# Symmetric_PS.net
KiCad netlist of a schematic drawn in Altium Designer
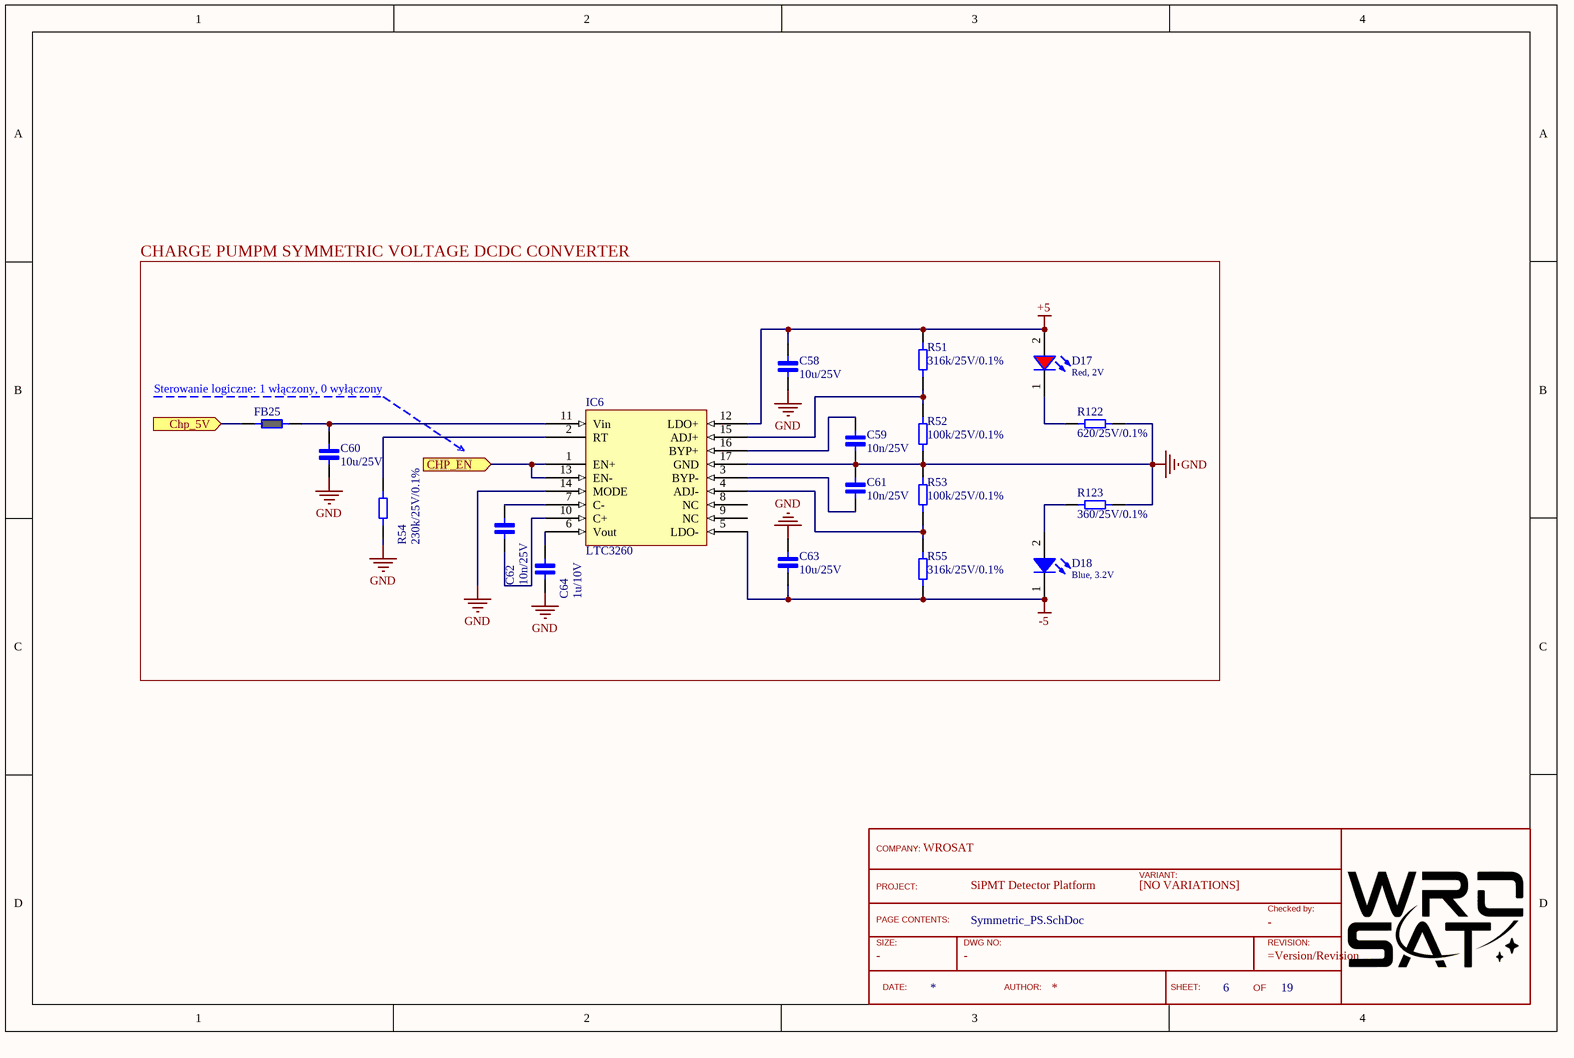
[diagram p0: Symmetric_PS.SchDoc]

(export (version "E")
  (design (tool "Eeschema 10.0.6"))
  (components
    (comp (ref "C58")
      (value "10u/25V")
      (footprint "CAP_0805")
      (description "Ceramic Capacitor 10uF / 0805 / 25V / ±5%, Wurth Elektronik MLCC")
      (libsource (lib "Cubesat_lib") (part "Cap_0805_10u_25v"))
    )
    (comp (ref "C59")
      (value "10n/25V")
      (footprint "Cap_0402")
      (description "Ceramic Capacitor 10n / 0402 / 25V / ±5%, Wurth Elektronik MLCC")
      (libsource (lib "Cubesat_lib") (part "Cap_0402_10n"))
    )
    (comp (ref "C60")
      (value "10u/25V")
      (footprint "CAP_0805")
      (description "Ceramic Capacitor 10uF / 0805 / 25V / ±5%, Wurth Elektronik MLCC")
      (libsource (lib "Cubesat_lib") (part "Cap_0805_10u_25v"))
    )
    (comp (ref "C61")
      (value "10n/25V")
      (footprint "Cap_0402")
      (description "Ceramic Capacitor 10n / 0402 / 25V / ±5%, Wurth Elektronik MLCC")
      (libsource (lib "Cubesat_lib") (part "Cap_0402_10n"))
    )
    (comp (ref "C62")
      (value "10n/25V")
      (footprint "Cap_0402")
      (description "Ceramic Capacitor 10n / 0402 / 25V / ±5%, Wurth Elektronik MLCC")
      (libsource (lib "Cubesat_lib") (part "Cap_0402_10n"))
    )
    (comp (ref "C63")
      (value "10u/25V")
      (footprint "CAP_0805")
      (description "Ceramic Capacitor 10uF / 0805 / 25V / ±5%, Wurth Elektronik MLCC")
      (libsource (lib "Cubesat_lib") (part "Cap_0805_10u_25v"))
    )
    (comp (ref "C64")
      (value "1u/10V")
      (footprint "Cap_0402")
      (description "Ceramic Capacitor 1uF / 0402 / 10V / ±5%, Wurth Elektronik MLCC")
      (libsource (lib "Cubesat_lib") (part "Cap_0402_1u"))
    )
    (comp (ref "D17")
      (value "Red, 2V")
      (footprint "WL-SMCW_0603_H=0.7mm")
      (description "WL-SMCW SMT Mono-color Chip LED Waterclear, size 0603, Red, 2V, 140deg")
      (fields (field (name "PART NUMBER") "150060RS75000") (field (name "PUBLISHER") "Wurth Elektronik"))
      (libsource (lib "LEDS") (part "150060RS75000"))
    )
    (comp (ref "D18")
      (value "Blue, 3.2V")
      (footprint "WL-SMCW_0603_H=0.7mm")
      (description "WL-SMCW SMT Mono-color Chip LED Waterclear, size 0603, Blue, 3.2V, 140deg")
      (fields (field (name "PART NUMBER") "150060BS75000") (field (name "PUBLISHER") "Wurth Elektronik"))
      (libsource (lib "LEDS") (part "150060BS75000"))
    )
    (comp (ref "FB25")
      (value "Ferrite_bead_0402")
      (footprint "FERRITE_0402")
      (description "Ferrite bead, wurth 74269241102")
      (libsource (lib "Cubesat_lib") (part "Ferrite_bead_0402"))
    )
    (comp (ref "IC6")
      (value "LTC3260")
      (footprint "MSOP-16")
      (description "Charge pump, low noise")
      (libsource (lib "Cubesat_lib") (part "LTC3260"))
    )
    (comp (ref "R51")
      (value "316k/25V/0.1%")
      (footprint "RES_0402")
      (description "Vishay, thin film resistor 316k/25V/0.1%")
      (libsource (lib "Cubesat_lib") (part "Res_0402_316k"))
    )
    (comp (ref "R52")
      (value "100k/25V/0.1%")
      (footprint "RES_0402")
      (description "Vishay, thin film resistor 100k/25V/0.1%")
      (libsource (lib "Cubesat_lib") (part "Res_0402_100k"))
    )
    (comp (ref "R53")
      (value "100k/25V/0.1%")
      (footprint "RES_0402")
      (description "Vishay, thin film resistor 100k/25V/0.1%")
      (libsource (lib "Cubesat_lib") (part "Res_0402_100k"))
    )
    (comp (ref "R54")
      (value "230k/25V/0.1%")
      (footprint "RES_0402")
      (description "Vishay, thin film resistor 230k/25V/0.1%")
      (libsource (lib "Cubesat_lib") (part "Res_0402_230k"))
    )
    (comp (ref "R55")
      (value "316k/25V/0.1%")
      (footprint "RES_0402")
      (description "Vishay, thin film resistor 316k/25V/0.1%")
      (libsource (lib "Cubesat_lib") (part "Res_0402_316k"))
    )
    (comp (ref "R122")
      (value "620/25V/0.1%")
      (footprint "RES_0402")
      (description "Vishay, thin film resistor 1/25V/0.1%")
      (libsource (lib "") (part "Res_0402_1_1"))
    )
    (comp (ref "R123")
      (value "360/25V/0.1%")
      (footprint "RES_0402")
      (description "Vishay, thin film resistor 1/25V/0.1%")
      (libsource (lib "Cubesat_lib") (part "Res_0402_1"))
    )
  )
  (nets
    (net (code "1") (name "+5") (class "Default")
      (node (ref "C58") (pin "2") (pinfunction "2_2") (pintype "passive"))
      (node (ref "D17") (pin "2") (pinfunction "A_2") (pintype "passive"))
      (node (ref "IC6") (pin "12") (pinfunction "LDO+_12") (pintype "input"))
      (node (ref "R51") (pin "2") (pinfunction "2_2") (pintype "passive"))
    )
    (net (code "2") (name "-5") (class "Default")
      (node (ref "C63") (pin "1") (pinfunction "1_1") (pintype "passive"))
      (node (ref "D18") (pin "1") (pinfunction "K_1") (pintype "passive"))
      (node (ref "IC6") (pin "5") (pinfunction "LDO-_5") (pintype "input"))
      (node (ref "R55") (pin "1") (pinfunction "1_1") (pintype "passive"))
    )
    (net (code "3") (name "/CHP_EN") (class "Default")
      (node (ref "IC6") (pin "1") (pinfunction "EN+_1") (pintype "passive"))
      (node (ref "IC6") (pin "13") (pinfunction "EN-_13") (pintype "input"))
    )
    (net (code "4") (name "/Chp_5V") (class "Default")
      (node (ref "FB25") (pin "1") (pinfunction "1_1") (pintype "passive"))
    )
    (net (code "5") (name "GND") (class "Default")
      (node (ref "C58") (pin "1") (pinfunction "1_1") (pintype "passive"))
      (node (ref "C59") (pin "1") (pinfunction "1_1") (pintype "passive"))
      (node (ref "C60") (pin "1") (pinfunction "1_1") (pintype "passive"))
      (node (ref "C61") (pin "2") (pinfunction "2_2") (pintype "passive"))
      (node (ref "C63") (pin "2") (pinfunction "2_2") (pintype "passive"))
      (node (ref "C64") (pin "1") (pinfunction "1_1") (pintype "passive"))
      (node (ref "IC6") (pin "14") (pinfunction "MODE_14") (pintype "input"))
      (node (ref "IC6") (pin "17") (pinfunction "GND_17") (pintype "input"))
      (node (ref "R122") (pin "1") (pinfunction "1_1") (pintype "passive"))
      (node (ref "R123") (pin "2") (pinfunction "2_2") (pintype "passive"))
      (node (ref "R52") (pin "1") (pinfunction "1_1") (pintype "passive"))
      (node (ref "R53") (pin "2") (pinfunction "2_2") (pintype "passive"))
      (node (ref "R54") (pin "1") (pinfunction "1_1") (pintype "passive"))
    )
    (net (code "6") (name "Net-(D17-K)") (class "Default")
      (node (ref "D17") (pin "1") (pinfunction "K_1") (pintype "passive"))
      (node (ref "R122") (pin "2") (pinfunction "2_2") (pintype "passive"))
    )
    (net (code "7") (name "Net-(D18-A)") (class "Default")
      (node (ref "D18") (pin "2") (pinfunction "A_2") (pintype "passive"))
      (node (ref "R123") (pin "1") (pinfunction "1_1") (pintype "passive"))
    )
    (net (code "8") (name "Net-(IC6-ADJ+)") (class "Default")
      (node (ref "IC6") (pin "15") (pinfunction "ADJ+_15") (pintype "input"))
      (node (ref "R51") (pin "1") (pinfunction "1_1") (pintype "passive"))
      (node (ref "R52") (pin "2") (pinfunction "2_2") (pintype "passive"))
    )
    (net (code "9") (name "Net-(IC6-ADJ-)") (class "Default")
      (node (ref "IC6") (pin "4") (pinfunction "ADJ-_4") (pintype "input"))
      (node (ref "R53") (pin "1") (pinfunction "1_1") (pintype "passive"))
      (node (ref "R55") (pin "2") (pinfunction "2_2") (pintype "passive"))
    )
    (net (code "10") (name "Net-(IC6-BYP+)") (class "Default")
      (node (ref "C59") (pin "2") (pinfunction "2_2") (pintype "passive"))
      (node (ref "IC6") (pin "16") (pinfunction "BYP+_16") (pintype "input"))
    )
    (net (code "11") (name "Net-(IC6-BYP-)") (class "Default")
      (node (ref "C61") (pin "1") (pinfunction "1_1") (pintype "passive"))
      (node (ref "IC6") (pin "3") (pinfunction "BYP-_3") (pintype "input"))
    )
    (net (code "12") (name "Net-(IC6-C+)") (class "Default")
      (node (ref "C62") (pin "1") (pinfunction "1_1") (pintype "passive"))
      (node (ref "IC6") (pin "10") (pinfunction "C+_10") (pintype "input"))
    )
    (net (code "13") (name "Net-(IC6-C-)") (class "Default")
      (node (ref "C62") (pin "2") (pinfunction "2_2") (pintype "passive"))
      (node (ref "IC6") (pin "7") (pinfunction "C-_7") (pintype "input"))
    )
    (net (code "14") (name "Net-(IC6-RT)") (class "Default")
      (node (ref "IC6") (pin "2") (pinfunction "RT_2") (pintype "passive"))
      (node (ref "R54") (pin "2") (pinfunction "2_2") (pintype "passive"))
    )
    (net (code "15") (name "Net-(IC6-Vin)") (class "Default")
      (node (ref "C60") (pin "2") (pinfunction "2_2") (pintype "passive"))
      (node (ref "FB25") (pin "2") (pinfunction "2_2") (pintype "passive"))
      (node (ref "IC6") (pin "11") (pinfunction "Vin_11") (pintype "input"))
    )
    (net (code "16") (name "Net-(IC6-Vout)") (class "Default")
      (node (ref "C64") (pin "2") (pinfunction "2_2") (pintype "passive"))
      (node (ref "IC6") (pin "6") (pinfunction "Vout_6") (pintype "input"))
    )
    (net (code "17") (name "unconnected-(IC6-NC-Pad8)") (class "Default")
      (node (ref "IC6") (pin "8") (pinfunction "NC_8") (pintype "input"))
    )
    (net (code "18") (name "unconnected-(IC6-NC-Pad9)") (class "Default")
      (node (ref "IC6") (pin "9") (pinfunction "NC_9") (pintype "input"))
    )
  )
)
